# STM32F103C6T7A.net
KiCad netlist of a schematic drawn in Altium Designer
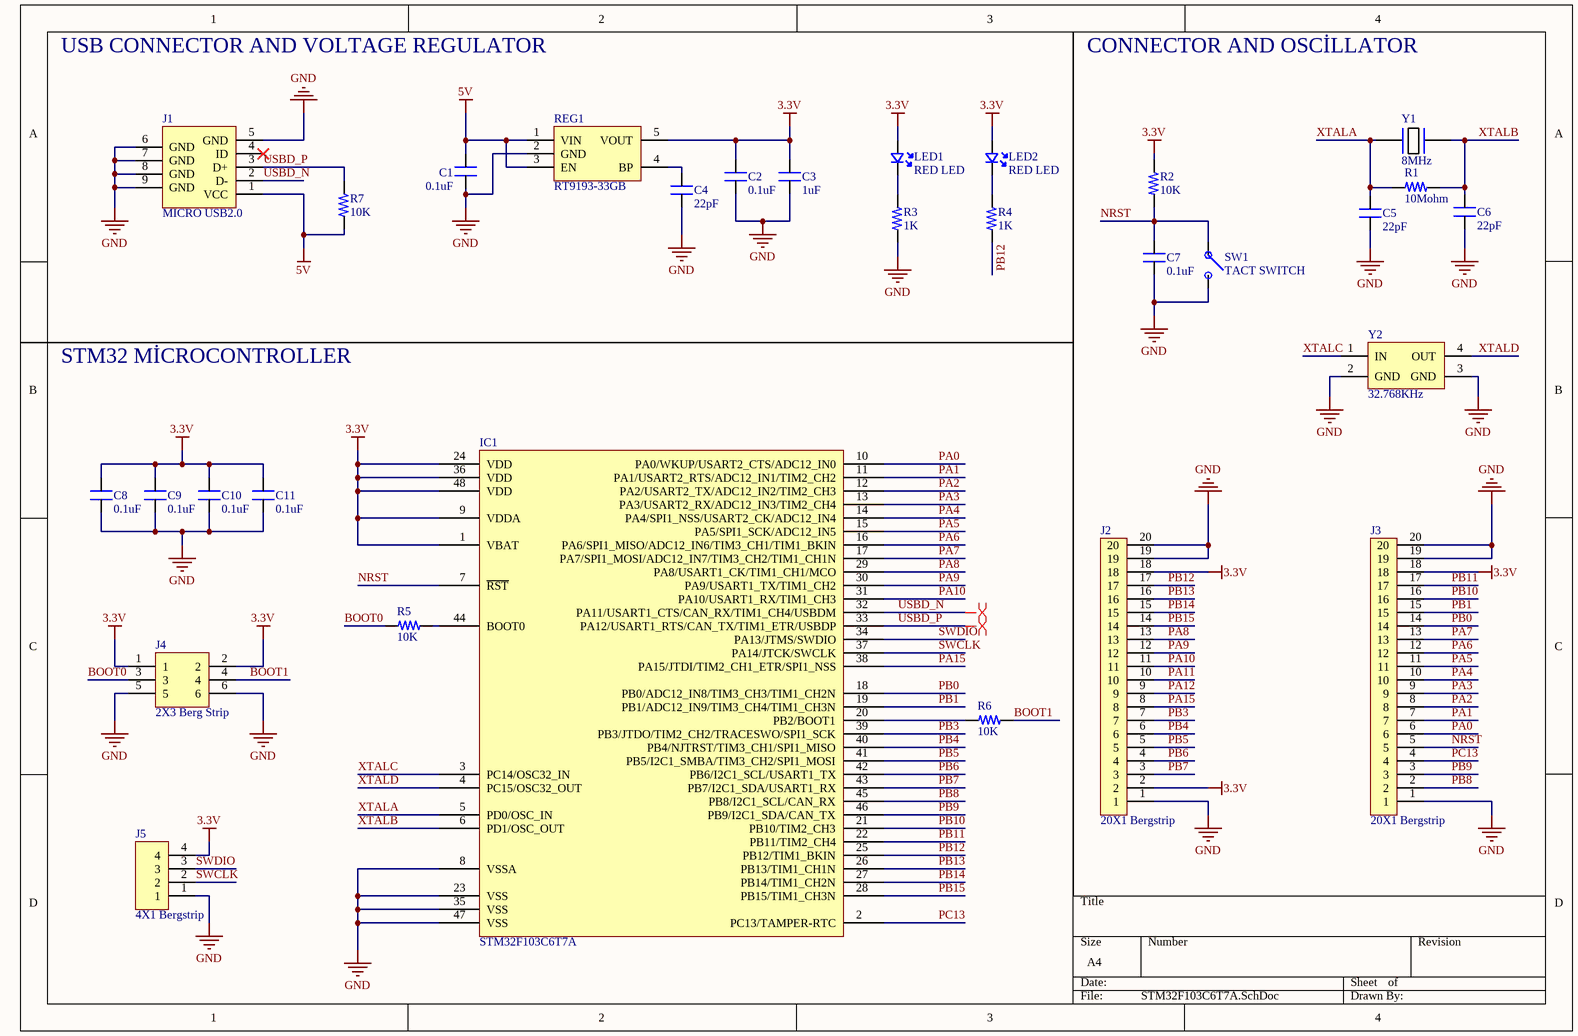
[diagram p0: STM32F103C6T7A.SchDoc]

(export (version "E")
  (design (tool "Eeschema 10.0.6"))
  (components
    (comp (ref "C1")
      (value "0.1uF")
      (footprint "CAP_0805")
      (description "0.1µF ±5% 50V Ceramic Capacitor X7R 0805 (2012 Metric)")
      (fields
        (field (name "MANUFACTURER") "KEMET")
        (field (name "MANUFACTURING PART NUMBER") "C0805C104J5RACTU")
      )
      (libsource (lib "STM_INT_LIB") (part "CAP_0.1uF-50V-5%-0805"))
    )
    (comp (ref "C2")
      (value "0.1uF")
      (footprint "CAP_0805")
      (description "0.1µF ±5% 50V Ceramic Capacitor X7R 0805 (2012 Metric)")
      (fields
        (field (name "MANUFACTURER") "KEMET")
        (field (name "MANUFACTURING PART NUMBER") "C0805C104J5RACTU")
      )
      (libsource (lib "STM_INT_LIB") (part "CAP_0.1uF-50V-5%-0805"))
    )
    (comp (ref "C3")
      (value "1uF")
      (footprint "CAP_0805")
      (description "1µF ±5% 50V Ceramic Capacitor X7R 0805 (2012 Metric)")
      (fields
        (field (name "MANUFACTURER") "Yageo")
        (field (name "MANUFACTURING PART NUMBER") "CC0805JKX7R9BB105")
      )
      (libsource (lib "STM_INT_LIB") (part "CAP_1uF-50V-5%-0805"))
    )
    (comp (ref "C4")
      (value "22pF")
      (footprint "CAP_0805")
      (description "22pF ±5% 50V Ceramic Capacitor C0G, NP0 0805 (2012 Metric)")
      (fields
        (field (name "MANUFACTURER") "KEMET")
        (field (name "MANUFACTURER PART NUMBER") "C0805C220J5GACTU")
      )
      (libsource (lib "STM_INT_LIB") (part "CAP_22pF-50V-5%-0805"))
    )
    (comp (ref "C5")
      (value "22pF")
      (footprint "CAP_0805")
      (description "22pF ±5% 50V Ceramic Capacitor C0G, NP0 0805 (2012 Metric)")
      (fields
        (field (name "MANUFACTURER") "KEMET")
        (field (name "MANUFACTURER PART NUMBER") "C0805C220J5GACTU")
      )
      (libsource (lib "STM_INT_LIB") (part "CAP_22pF-50V-5%-0805"))
    )
    (comp (ref "C6")
      (value "22pF")
      (footprint "CAP_0805")
      (description "22pF ±5% 50V Ceramic Capacitor C0G, NP0 0805 (2012 Metric)")
      (fields
        (field (name "MANUFACTURER") "KEMET")
        (field (name "MANUFACTURER PART NUMBER") "C0805C220J5GACTU")
      )
      (libsource (lib "STM_INT_LIB") (part "CAP_22pF-50V-5%-0805"))
    )
    (comp (ref "C7")
      (value "0.1uF")
      (footprint "CAP_0805")
      (description "0.1µF ±5% 50V Ceramic Capacitor X7R 0805 (2012 Metric)")
      (fields
        (field (name "MANUFACTURER") "KEMET")
        (field (name "MANUFACTURING PART NUMBER") "C0805C104J5RACTU")
      )
      (libsource (lib "STM_INT_LIB") (part "CAP_0.1uF-50V-5%-0805"))
    )
    (comp (ref "C8")
      (value "0.1uF")
      (footprint "CAP_0805")
      (description "0.1µF ±5% 50V Ceramic Capacitor X7R 0805 (2012 Metric)")
      (fields
        (field (name "MANUFACTURER") "KEMET")
        (field (name "MANUFACTURING PART NUMBER") "C0805C104J5RACTU")
      )
      (libsource (lib "STM_INT_LIB") (part "CAP_0.1uF-50V-5%-0805"))
    )
    (comp (ref "C9")
      (value "0.1uF")
      (footprint "CAP_0805")
      (description "0.1µF ±5% 50V Ceramic Capacitor X7R 0805 (2012 Metric)")
      (fields
        (field (name "MANUFACTURER") "KEMET")
        (field (name "MANUFACTURING PART NUMBER") "C0805C104J5RACTU")
      )
      (libsource (lib "STM_INT_LIB") (part "CAP_0.1uF-50V-5%-0805"))
    )
    (comp (ref "C10")
      (value "0.1uF")
      (footprint "CAP_0805")
      (description "0.1µF ±5% 50V Ceramic Capacitor X7R 0805 (2012 Metric)")
      (fields
        (field (name "MANUFACTURER") "KEMET")
        (field (name "MANUFACTURING PART NUMBER") "C0805C104J5RACTU")
      )
      (libsource (lib "STM_INT_LIB") (part "CAP_0.1uF-50V-5%-0805"))
    )
    (comp (ref "C11")
      (value "0.1uF")
      (footprint "CAP_0805")
      (description "0.1µF ±5% 50V Ceramic Capacitor X7R 0805 (2012 Metric)")
      (fields
        (field (name "MANUFACTURER") "KEMET")
        (field (name "MANUFACTURING PART NUMBER") "C0805C104J5RACTU")
      )
      (libsource (lib "STM_INT_LIB") (part "CAP_0.1uF-50V-5%-0805"))
    )
    (comp (ref "IC1")
      (value "STM32F103C6T7A")
      (footprint "ST LQFP-48 7X7MM")
      (description "IC MCU 32BIT 32KB FLASH 48LQFP")
      (fields (field (name "MANUFACTURER") "STMicroelectronics"))
      (libsource (lib "Celestial Altium Library - altium_library") (part "ST STM32F103 48PIN"))
    )
    (comp (ref "J1")
      (value "MICRO USB2.0")
      (footprint "CON_10118192-0001LF_SMD")
      (description "USB - micro B USB 2.0 Receptacle Connector 5 Position Surface Mount, Right Angle")
      (fields
        (field (name "MANUFACTURER") "Amphenol ICC (FCI)")
        (field (name "MANUFACTURING PART NUMBER") "10118192-0002LF")
      )
      (libsource (lib "STM_INT_LIB") (part "CON-USB_10118192-0002LF-SMD"))
    )
    (comp (ref "J2")
      (value "20X1 Bergstrip")
      (footprint "CON20_100_40D72_TH_ST")
      (description "20 pin, 1 row, 2.54mm pitch bergstrip")
      (fields (field (name "MANUFACTURER") "NA"))
      (libsource (lib "STM_INT_LIB") (part "CON-BS-PLG_20X1-100-TH-ST"))
    )
    (comp (ref "J3")
      (value "20X1 Bergstrip")
      (footprint "CON20_100_40D72_TH_ST")
      (description "20 pin, 1 row, 2.54mm pitch bergstrip")
      (fields (field (name "MANUFACTURER") "NA"))
      (libsource (lib "STM_INT_LIB") (part "CON-BS-PLG_20X1-100-TH-ST"))
    )
    (comp (ref "J4")
      (value "2X3 Berg Strip")
      (footprint "CON6_100_59D78_TH_ST_Duplicate")
      (description "6 pin, 2 row, 2.54mm pitch bergstrip")
      (fields (field (name "MANUFACTURER") "NA"))
      (libsource (lib "STM_INT_LIB") (part "CON-BS-PLG_2X3-100-TH-ST"))
    )
    (comp (ref "J5")
      (value "4X1 Bergstrip")
      (footprint "CON4_100_40D72_TH_ST_MALE")
      (description "4 pin, 1 row, 2.54mm pitch bergstrip")
      (fields (field (name "MANUFACTURER") "NA"))
      (libsource (lib "STM_INT_LIB") (part "CON-BS-PLG_4X1-100-TH-ST"))
    )
    (comp (ref "LED1")
      (value "RED LED")
      (footprint "LED_0805")
      (description "Red 621nm LED Indication - Discrete 2V 0805 (2012 Metric)")
      (fields
        (field (name "MANUFACTURER") "Lite-On Inc.")
        (field (name "MANUFACTURER PART NUMBER") "LTST-C170EKT")
      )
      (libsource (lib "STM_INT_LIB") (part "LED-RED_10mA-0805"))
    )
    (comp (ref "LED2")
      (value "RED LED")
      (footprint "LED_0805")
      (description "Red 621nm LED Indication - Discrete 2V 0805 (2012 Metric)")
      (fields
        (field (name "MANUFACTURER") "Lite-On Inc.")
        (field (name "MANUFACTURER PART NUMBER") "LTST-C170EKT")
      )
      (libsource (lib "STM_INT_LIB") (part "LED-RED_10mA-0805"))
    )
    (comp (ref "R1")
      (value "10Mohm")
      (footprint "RES_0805")
      (fields
        (field (name "MANUFACTURER") "Rohm Semiconductor")
        (field (name "MANUFACTURING PART NUMBER") "KTR10EZPF1005")
      )
      (libsource (lib "STM_INT_LIB") (part "RES_10MOHM-0.125W-1%-0805"))
    )
    (comp (ref "R2")
      (value "10K")
      (footprint "RES_0805")
      (description "10 kOhms ±1% 0.125W, 1/8W Chip Resistor 0805 (2012 Metric) Moisture Resistant Thick Film")
      (fields
        (field (name "MANUFACTURER") "Yageo")
        (field (name "MANUFACTURING PART NUMBER") "RC0805FR-0710KL")
      )
      (libsource (lib "STM_INT_LIB") (part "RES_10K-0.125W-1%-0805"))
    )
    (comp (ref "R3")
      (value "1K")
      (footprint "RES_0805")
      (description "1 kOhms ±1% 0.125W, 1/8W Chip Resistor 0805 (2012 Metric) Moisture Resistant Thick Film")
      (fields (field (name "MANUFACTURER") "垈㎵á") (field (name "MANUFACTURER PART NUMBER") "RC0805FR-071KL"))
      (libsource (lib "STM_INT_LIB") (part "RES_1K-0.125W-1%-0805"))
    )
    (comp (ref "R4")
      (value "1K")
      (footprint "RES_0805")
      (description "1 kOhms ±1% 0.125W, 1/8W Chip Resistor 0805 (2012 Metric) Moisture Resistant Thick Film")
      (fields (field (name "MANUFACTURER") "垈㎵á") (field (name "MANUFACTURER PART NUMBER") "RC0805FR-071KL"))
      (libsource (lib "STM_INT_LIB") (part "RES_1K-0.125W-1%-0805"))
    )
    (comp (ref "R5")
      (value "10K")
      (footprint "RES_0805")
      (description "10 kOhms ±1% 0.125W, 1/8W Chip Resistor 0805 (2012 Metric) Moisture Resistant Thick Film")
      (fields
        (field (name "MANUFACTURER") "Yageo")
        (field (name "MANUFACTURING PART NUMBER") "RC0805FR-0710KL")
      )
      (libsource (lib "STM_INT_LIB") (part "RES_10K-0.125W-1%-0805"))
    )
    (comp (ref "R6")
      (value "10K")
      (footprint "RES_0805")
      (description "10 kOhms ±1% 0.125W, 1/8W Chip Resistor 0805 (2012 Metric) Moisture Resistant Thick Film")
      (fields
        (field (name "MANUFACTURER") "Yageo")
        (field (name "MANUFACTURING PART NUMBER") "RC0805FR-0710KL")
      )
      (libsource (lib "STM_INT_LIB") (part "RES_10K-0.125W-1%-0805"))
    )
    (comp (ref "R7")
      (value "10K")
      (footprint "RES_0805")
      (description "10 kOhms ±1% 0.125W, 1/8W Chip Resistor 0805 (2012 Metric) Moisture Resistant Thick Film")
      (fields
        (field (name "MANUFACTURER") "Yageo")
        (field (name "MANUFACTURING PART NUMBER") "RC0805FR-0710KL")
      )
      (libsource (lib "STM_INT_LIB") (part "RES_10K-0.125W-1%-0805"))
    )
    (comp (ref "REG1")
      (value "RT9193-33GB")
      (footprint "SOT23-5")
      (description "Linear Voltage Regulator IC 1 Output 300mA SOT-23-5")
      (fields (field (name "MANUFACTURER") "Richtek USA Inc."))
      (libsource (lib "STM_INT_LIB") (part "REG_3.3V-5.5V-0.3A-SOT-23-5"))
    )
    (comp (ref "SW1")
      (value "TACT SWITCH")
      (footprint "SW_342_SMD")
      (description "Tactile Switch SPST-NO Top Actuated Surface Mount")
      (fields (field (name "MANUFACTURER") "C&K") (field (name "MANUFACTURING PART NUMBER") "KSR223GLFG"))
      (libsource (lib "STM_INT_LIB") (part "SW_KSR223GLFG-SMD"))
    )
    (comp (ref "Y1")
      (value "8MHz")
      (footprint "XTAL_314_240X47_SMD")
      (description "Crystals 8MHz 22pF -20C 70C")
      (fields
        (field (name "MANUFACTURER") "IQD Frequency Products")
        (field (name "MANUFACTURING PART NUMBER") "LFXTAL030234Reel")
      )
      (libsource (lib "STM_INT_LIB") (part "XTAL_8MHZ-LFXTAL030234"))
    )
    (comp (ref "Y2")
      (value "32.768KHz")
      (footprint "XTAL_MC-405 32.7680K-G3")
      (description "Crystals SMD AT XTL MHZ +/-50PPM 12.5 PF 250 T/R")
      (fields
        (field (name "MANUFACTURER") "Epson")
        (field (name "MANUFACTURING PART NUMBER") "MC-405 32.7680K-G3: ROHS")
      )
      (libsource (lib "STM_INT_LIB") (part "XTAL_32.768KHz-MC-405 32.7680K-G3"))
    )
  )
  (nets
    (net (code "1") (name "/BOOT0") (class "Default")
      (node (ref "J4") (pin "3") (pinfunction "3_3") (pintype "passive"))
      (node (ref "R5") (pin "1") (pinfunction "1_1") (pintype "passive"))
    )
    (net (code "2") (name "/BOOT1") (class "Default")
      (node (ref "J4") (pin "4") (pinfunction "4_4") (pintype "passive"))
      (node (ref "R6") (pin "2") (pinfunction "2_2") (pintype "passive"))
    )
    (net (code "3") (name "/NRST") (class "Default")
      (node (ref "C7") (pin "2") (pinfunction "2_2") (pintype "passive"))
      (node (ref "IC1") (pin "7") (pinfunction "~{RST}_7") (pintype "passive"))
      (node (ref "J3") (pin "5") (pinfunction "5_5") (pintype "passive"))
      (node (ref "R2") (pin "1") (pinfunction "1_1") (pintype "passive"))
      (node (ref "SW1") (pin "1") (pinfunction "1_1") (pintype "passive"))
    )
    (net (code "4") (name "/PA0") (class "Default")
      (node (ref "IC1") (pin "10") (pinfunction "PA0/WKUP/USART2_CTS/ADC12_IN0_10") (pintype "passive"))
      (node (ref "J3") (pin "6") (pinfunction "6_6") (pintype "passive"))
    )
    (net (code "5") (name "/PA1") (class "Default")
      (node (ref "IC1") (pin "11") (pinfunction "PA1/USART2_RTS/ADC12_IN1/TIM2_CH2_11") (pintype "passive"))
      (node (ref "J3") (pin "7") (pinfunction "7_7") (pintype "passive"))
    )
    (net (code "6") (name "/PA2") (class "Default")
      (node (ref "IC1") (pin "12") (pinfunction "PA2/USART2_TX/ADC12_IN2/TIM2_CH3_12") (pintype "passive"))
      (node (ref "J3") (pin "8") (pinfunction "8_8") (pintype "passive"))
    )
    (net (code "7") (name "/PA3") (class "Default")
      (node (ref "IC1") (pin "13") (pinfunction "PA3/USART2_RX/ADC12_IN3/TIM2_CH4_13") (pintype "passive"))
      (node (ref "J3") (pin "9") (pinfunction "9_9") (pintype "passive"))
    )
    (net (code "8") (name "/PA4") (class "Default")
      (node (ref "IC1") (pin "14") (pinfunction "PA4/SPI1_NSS/USART2_CK/ADC12_IN4_14") (pintype "passive"))
      (node (ref "J3") (pin "10") (pinfunction "10_10") (pintype "passive"))
    )
    (net (code "9") (name "/PA5") (class "Default")
      (node (ref "IC1") (pin "15") (pinfunction "PA5/SPI1_SCK/ADC12_IN5_15") (pintype "passive"))
      (node (ref "J3") (pin "11") (pinfunction "11_11") (pintype "passive"))
    )
    (net (code "10") (name "/PA6") (class "Default")
      (node (ref "IC1") (pin "16") (pinfunction "PA6/SPI1_MISO/ADC12_IN6/TIM3_CH1/TIM1_BKIN_16") (pintype "passive"))
      (node (ref "J3") (pin "12") (pinfunction "12_12") (pintype "passive"))
    )
    (net (code "11") (name "/PA7") (class "Default")
      (node (ref "IC1") (pin "17") (pinfunction "PA7/SPI1_MOSI/ADC12_IN7/TIM3_CH2/TIM1_CH1N_17") (pintype "passive"))
      (node (ref "J3") (pin "13") (pinfunction "13_13") (pintype "passive"))
    )
    (net (code "12") (name "/PA8") (class "Default")
      (node (ref "IC1") (pin "29") (pinfunction "PA8/USART1_CK/TIM1_CH1/MCO_29") (pintype "passive"))
      (node (ref "J2") (pin "13") (pinfunction "13_13") (pintype "passive"))
    )
    (net (code "13") (name "/PA9") (class "Default")
      (node (ref "IC1") (pin "30") (pinfunction "PA9/USART1_TX/TIM1_CH2_30") (pintype "passive"))
      (node (ref "J2") (pin "12") (pinfunction "12_12") (pintype "passive"))
    )
    (net (code "14") (name "/PA10") (class "Default")
      (node (ref "IC1") (pin "31") (pinfunction "PA10/USART1_RX/TIM1_CH3_31") (pintype "passive"))
      (node (ref "J2") (pin "11") (pinfunction "11_11") (pintype "passive"))
    )
    (net (code "15") (name "/PA11") (class "Default")
      (node (ref "J2") (pin "10") (pinfunction "10_10") (pintype "passive"))
    )
    (net (code "16") (name "/PA12") (class "Default")
      (node (ref "J2") (pin "9") (pinfunction "9_9") (pintype "passive"))
    )
    (net (code "17") (name "/PA15") (class "Default")
      (node (ref "IC1") (pin "38") (pinfunction "PA15/JTDI/TIM2_CH1_ETR/SPI1_NSS_38") (pintype "passive"))
      (node (ref "J2") (pin "8") (pinfunction "8_8") (pintype "passive"))
    )
    (net (code "18") (name "/PB0") (class "Default")
      (node (ref "IC1") (pin "18") (pinfunction "PB0/ADC12_IN8/TIM3_CH3/TIM1_CH2N_18") (pintype "passive"))
      (node (ref "J3") (pin "14") (pinfunction "14_14") (pintype "passive"))
    )
    (net (code "19") (name "/PB1") (class "Default")
      (node (ref "IC1") (pin "19") (pinfunction "PB1/ADC12_IN9/TIM3_CH4/TIM1_CH3N_19") (pintype "passive"))
      (node (ref "J3") (pin "15") (pinfunction "15_15") (pintype "passive"))
    )
    (net (code "20") (name "/PB3") (class "Default")
      (node (ref "IC1") (pin "39") (pinfunction "PB3/JTDO/TIM2_CH2/TRACESWO/SPI1_SCK_39") (pintype "passive"))
      (node (ref "J2") (pin "7") (pinfunction "7_7") (pintype "passive"))
    )
    (net (code "21") (name "/PB4") (class "Default")
      (node (ref "IC1") (pin "40") (pinfunction "PB4/NJTRST/TIM3_CH1/SPI1_MISO_40") (pintype "passive"))
      (node (ref "J2") (pin "6") (pinfunction "6_6") (pintype "passive"))
    )
    (net (code "22") (name "/PB5") (class "Default")
      (node (ref "IC1") (pin "41") (pinfunction "PB5/I2C1_SMBA/TIM3_CH2/SPI1_MOSI_41") (pintype "passive"))
      (node (ref "J2") (pin "5") (pinfunction "5_5") (pintype "passive"))
    )
    (net (code "23") (name "/PB6") (class "Default")
      (node (ref "IC1") (pin "42") (pinfunction "PB6/I2C1_SCL/USART1_TX_42") (pintype "passive"))
      (node (ref "J2") (pin "4") (pinfunction "4_4") (pintype "passive"))
    )
    (net (code "24") (name "/PB7") (class "Default")
      (node (ref "IC1") (pin "43") (pinfunction "PB7/I2C1_SDA/USART1_RX_43") (pintype "passive"))
      (node (ref "J2") (pin "3") (pinfunction "3_3") (pintype "passive"))
    )
    (net (code "25") (name "/PB8") (class "Default")
      (node (ref "IC1") (pin "45") (pinfunction "PB8/I2C1_SCL/CAN_RX_45") (pintype "passive"))
      (node (ref "J3") (pin "2") (pinfunction "2_2") (pintype "passive"))
    )
    (net (code "26") (name "/PB9") (class "Default")
      (node (ref "IC1") (pin "46") (pinfunction "PB9/I2C1_SDA/CAN_TX_46") (pintype "passive"))
      (node (ref "J3") (pin "3") (pinfunction "3_3") (pintype "passive"))
    )
    (net (code "27") (name "/PB10") (class "Default")
      (node (ref "IC1") (pin "21") (pinfunction "PB10/TIM2_CH3_21") (pintype "passive"))
      (node (ref "J3") (pin "16") (pinfunction "16_16") (pintype "passive"))
    )
    (net (code "28") (name "/PB11") (class "Default")
      (node (ref "IC1") (pin "22") (pinfunction "PB11/TIM2_CH4_22") (pintype "passive"))
      (node (ref "J3") (pin "17") (pinfunction "17_17") (pintype "passive"))
    )
    (net (code "29") (name "/PB12") (class "Default")
      (node (ref "IC1") (pin "25") (pinfunction "PB12/TIM1_BKIN_25") (pintype "passive"))
      (node (ref "J2") (pin "17") (pinfunction "17_17") (pintype "passive"))
      (node (ref "R4") (pin "1") (pinfunction "1_1") (pintype "passive"))
    )
    (net (code "30") (name "/PB13") (class "Default")
      (node (ref "IC1") (pin "26") (pinfunction "PB13/TIM1_CH1N_26") (pintype "passive"))
      (node (ref "J2") (pin "16") (pinfunction "16_16") (pintype "passive"))
    )
    (net (code "31") (name "/PB14") (class "Default")
      (node (ref "IC1") (pin "27") (pinfunction "PB14/TIM1_CH2N_27") (pintype "passive"))
      (node (ref "J2") (pin "15") (pinfunction "15_15") (pintype "passive"))
    )
    (net (code "32") (name "/PB15") (class "Default")
      (node (ref "IC1") (pin "28") (pinfunction "PB15/TIM1_CH3N_28") (pintype "passive"))
      (node (ref "J2") (pin "14") (pinfunction "14_14") (pintype "passive"))
    )
    (net (code "33") (name "/PC13") (class "Default")
      (node (ref "IC1") (pin "2") (pinfunction "PC13/TAMPER-RTC_2") (pintype "passive"))
      (node (ref "J3") (pin "4") (pinfunction "4_4") (pintype "passive"))
    )
    (net (code "34") (name "/SWCLK") (class "Default")
      (node (ref "IC1") (pin "37") (pinfunction "PA14/JTCK/SWCLK_37") (pintype "passive"))
      (node (ref "J5") (pin "2") (pinfunction "2_2") (pintype "passive"))
    )
    (net (code "35") (name "/SWDIO") (class "Default")
      (node (ref "IC1") (pin "34") (pinfunction "PA13/JTMS/SWDIO_34") (pintype "passive"))
      (node (ref "J5") (pin "3") (pinfunction "3_3") (pintype "passive"))
    )
    (net (code "36") (name "/USBD_N") (class "Default")
      (node (ref "IC1") (pin "32") (pinfunction "PA11/USART1_CTS/CAN_RX/TIM1_CH4/USBDM_32") (pintype "passive"))
      (node (ref "J1") (pin "2") (pinfunction "D-_2") (pintype "passive"))
    )
    (net (code "37") (name "/USBD_P") (class "Default")
      (node (ref "IC1") (pin "33") (pinfunction "PA12/USART1_RTS/CAN_TX/TIM1_ETR/USBDP_33") (pintype "passive"))
      (node (ref "J1") (pin "3") (pinfunction "D+_3") (pintype "passive"))
      (node (ref "R7") (pin "2") (pinfunction "2_2") (pintype "passive"))
    )
    (net (code "38") (name "/XTALA") (class "Default")
      (node (ref "C5") (pin "2") (pinfunction "2_2") (pintype "passive"))
      (node (ref "IC1") (pin "5") (pinfunction "PD0/OSC_IN_5") (pintype "passive"))
      (node (ref "R1") (pin "1") (pinfunction "1_1") (pintype "passive"))
      (node (ref "Y1") (pin "1") (pinfunction "1_1") (pintype "passive"))
    )
    (net (code "39") (name "/XTALB") (class "Default")
      (node (ref "C6") (pin "2") (pinfunction "2_2") (pintype "passive"))
      (node (ref "IC1") (pin "6") (pinfunction "PD1/OSC_OUT_6") (pintype "passive"))
      (node (ref "R1") (pin "2") (pinfunction "2_2") (pintype "passive"))
      (node (ref "Y1") (pin "2") (pinfunction "2_2") (pintype "passive"))
    )
    (net (code "40") (name "/XTALC") (class "Default")
      (node (ref "IC1") (pin "3") (pinfunction "PC14/OSC32_IN_3") (pintype "passive"))
      (node (ref "Y2") (pin "1") (pinfunction "IN_1") (pintype "passive"))
    )
    (net (code "41") (name "/XTALD") (class "Default")
      (node (ref "IC1") (pin "4") (pinfunction "PC15/OSC32_OUT_4") (pintype "passive"))
      (node (ref "Y2") (pin "4") (pinfunction "OUT_4") (pintype "passive"))
    )
    (net (code "42") (name "3.3V") (class "Default")
      (node (ref "C10") (pin "2") (pinfunction "2_2") (pintype "passive"))
      (node (ref "C11") (pin "2") (pinfunction "2_2") (pintype "passive"))
      (node (ref "C2") (pin "2") (pinfunction "2_2") (pintype "passive"))
      (node (ref "C3") (pin "2") (pinfunction "2_2") (pintype "passive"))
      (node (ref "C8") (pin "2") (pinfunction "2_2") (pintype "passive"))
      (node (ref "C9") (pin "2") (pinfunction "2_2") (pintype "passive"))
      (node (ref "IC1") (pin "1") (pinfunction "VBAT_1") (pintype "passive"))
      (node (ref "IC1") (pin "24") (pinfunction "VDD_24") (pintype "passive"))
      (node (ref "IC1") (pin "36") (pinfunction "VDD_36") (pintype "passive"))
      (node (ref "IC1") (pin "48") (pinfunction "VDD_48") (pintype "passive"))
      (node (ref "IC1") (pin "9") (pinfunction "VDDA_9") (pintype "passive"))
      (node (ref "J2") (pin "18") (pinfunction "18_18") (pintype "passive"))
      (node (ref "J2") (pin "2") (pinfunction "2_2") (pintype "passive"))
      (node (ref "J3") (pin "18") (pinfunction "18_18") (pintype "passive"))
      (node (ref "J4") (pin "1") (pinfunction "1_1") (pintype "passive"))
      (node (ref "J4") (pin "2") (pinfunction "2_2") (pintype "passive"))
      (node (ref "J5") (pin "4") (pinfunction "4_4") (pintype "passive"))
      (node (ref "LED1") (pin "A") (pinfunction "A_A") (pintype "passive"))
      (node (ref "LED2") (pin "A") (pinfunction "A_A") (pintype "passive"))
      (node (ref "R2") (pin "2") (pinfunction "2_2") (pintype "passive"))
      (node (ref "REG1") (pin "5") (pinfunction "VOUT_5") (pintype "passive"))
    )
    (net (code "43") (name "5V") (class "Default")
      (node (ref "C1") (pin "2") (pinfunction "2_2") (pintype "passive"))
      (node (ref "J1") (pin "1") (pinfunction "VCC_1") (pintype "passive"))
      (node (ref "R7") (pin "1") (pinfunction "1_1") (pintype "passive"))
      (node (ref "REG1") (pin "1") (pinfunction "VIN_1") (pintype "passive"))
      (node (ref "REG1") (pin "3") (pinfunction "EN_3") (pintype "passive"))
    )
    (net (code "44") (name "GND") (class "Default")
      (node (ref "C1") (pin "1") (pinfunction "1_1") (pintype "passive"))
      (node (ref "C10") (pin "1") (pinfunction "1_1") (pintype "passive"))
      (node (ref "C11") (pin "1") (pinfunction "1_1") (pintype "passive"))
      (node (ref "C2") (pin "1") (pinfunction "1_1") (pintype "passive"))
      (node (ref "C3") (pin "1") (pinfunction "1_1") (pintype "passive"))
      (node (ref "C4") (pin "1") (pinfunction "1_1") (pintype "passive"))
      (node (ref "C5") (pin "1") (pinfunction "1_1") (pintype "passive"))
      (node (ref "C6") (pin "1") (pinfunction "1_1") (pintype "passive"))
      (node (ref "C7") (pin "1") (pinfunction "1_1") (pintype "passive"))
      (node (ref "C8") (pin "1") (pinfunction "1_1") (pintype "passive"))
      (node (ref "C9") (pin "1") (pinfunction "1_1") (pintype "passive"))
      (node (ref "IC1") (pin "23") (pinfunction "VSS_23") (pintype "passive"))
      (node (ref "IC1") (pin "35") (pinfunction "VSS_35") (pintype "passive"))
      (node (ref "IC1") (pin "47") (pinfunction "VSS_47") (pintype "passive"))
      (node (ref "IC1") (pin "8") (pinfunction "VSSA_8") (pintype "passive"))
      (node (ref "J1") (pin "5") (pinfunction "GND_5") (pintype "passive"))
      (node (ref "J1") (pin "6") (pinfunction "GND_6") (pintype "passive"))
      (node (ref "J1") (pin "7") (pinfunction "GND_7") (pintype "passive"))
      (node (ref "J1") (pin "8") (pinfunction "GND_8") (pintype "passive"))
      (node (ref "J1") (pin "9") (pinfunction "GND_9") (pintype "passive"))
      (node (ref "J2") (pin "1") (pinfunction "1_1") (pintype "passive"))
      (node (ref "J2") (pin "19") (pinfunction "19_19") (pintype "passive"))
      (node (ref "J2") (pin "20") (pinfunction "20_20") (pintype "passive"))
      (node (ref "J3") (pin "1") (pinfunction "1_1") (pintype "passive"))
      (node (ref "J3") (pin "19") (pinfunction "19_19") (pintype "passive"))
      (node (ref "J3") (pin "20") (pinfunction "20_20") (pintype "passive"))
      (node (ref "J4") (pin "5") (pinfunction "5_5") (pintype "passive"))
      (node (ref "J4") (pin "6") (pinfunction "6_6") (pintype "passive"))
      (node (ref "J5") (pin "1") (pinfunction "1_1") (pintype "passive"))
      (node (ref "R3") (pin "1") (pinfunction "1_1") (pintype "passive"))
      (node (ref "REG1") (pin "2") (pinfunction "GND_2") (pintype "passive"))
      (node (ref "SW1") (pin "2") (pinfunction "2_2") (pintype "passive"))
      (node (ref "Y2") (pin "2") (pinfunction "GND_2") (pintype "passive"))
      (node (ref "Y2") (pin "3") (pinfunction "GND_3") (pintype "passive"))
    )
    (net (code "45") (name "Net-(IC1-BOOT0)") (class "Default")
      (node (ref "IC1") (pin "44") (pinfunction "BOOT0_44") (pintype "passive"))
      (node (ref "R5") (pin "2") (pinfunction "2_2") (pintype "passive"))
    )
    (net (code "46") (name "Net-(IC1-PB2{slash}BOOT1)") (class "Default")
      (node (ref "IC1") (pin "20") (pinfunction "PB2/BOOT1_20") (pintype "passive"))
      (node (ref "R6") (pin "1") (pinfunction "1_1") (pintype "passive"))
    )
    (net (code "47") (name "Net-(LED1-PadK)") (class "Default")
      (node (ref "LED1") (pin "K") (pinfunction "K_K") (pintype "passive"))
      (node (ref "R3") (pin "2") (pinfunction "2_2") (pintype "passive"))
    )
    (net (code "48") (name "Net-(LED2-PadK)") (class "Default")
      (node (ref "LED2") (pin "K") (pinfunction "K_K") (pintype "passive"))
      (node (ref "R4") (pin "2") (pinfunction "2_2") (pintype "passive"))
    )
    (net (code "49") (name "Net-(REG1-BP)") (class "Default")
      (node (ref "C4") (pin "2") (pinfunction "2_2") (pintype "passive"))
      (node (ref "REG1") (pin "4") (pinfunction "BP_4") (pintype "passive"))
    )
    (net (code "50") (name "unconnected-(J1-ID-Pad4)") (class "Default")
      (node (ref "J1") (pin "4") (pinfunction "ID_4") (pintype "passive+no_connect"))
    )
  )
)
